# SPI_Bus.net
KiCad netlist of a schematic drawn in Altium Designer
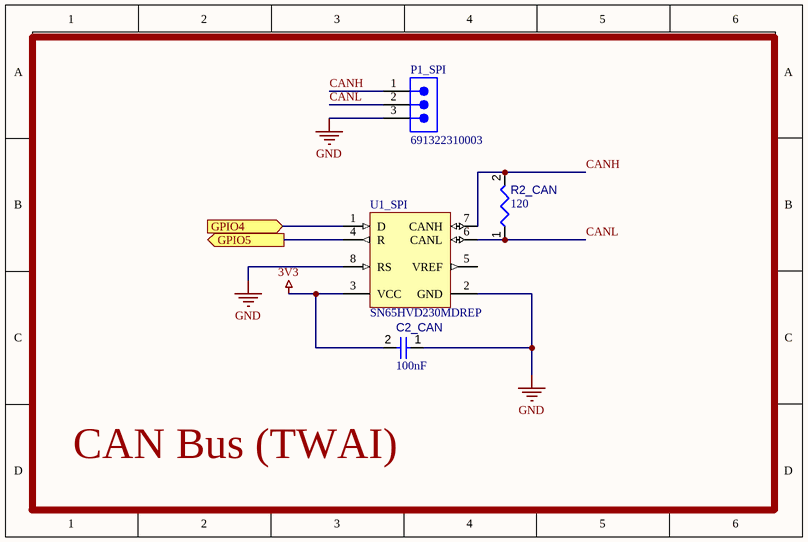
[diagram p0: SPI Bus.SchDoc]

(export (version "E")
  (design (tool "Eeschema 10.0.6"))
  (components
    (comp (ref "C2_CAN")
      (value "100nF")
      (footprint "CAPC0402(1005)60_L")
      (description "Chip Capacitor, 100nF +/-20%, 50V, 0402, Thickness 0.6 mm")
      (fields (field (name "TOLERANCE") "10%") (field (name "Comment") "Capacitor 100nF +/-20% 50V 0402"))
      (libsource (lib "Faiz Agunda") (part "CAP-NP-2"))
    )
    (comp (ref "P1_SPI")
      (value "691322310003")
      (footprint "691322310003")
      (description "322; 3.81mm Pitch Straight Pluggable Term Block; PCB Header; Through Hole; 3 Way")
      (fields (field (name "VOLTAGE") "300V"))
      (libsource (lib "Altium Content Vault") (part "TBL - 1R - 03P - Male"))
    )
    (comp (ref "R2_CAN")
      (value "120")
      (footprint "RESC0603(1608)_L")
      (description "Chip Resistor, 120 Ohms, +/-5 %, 0.1 W, -55 to 155 degC, 0603")
      (fields (field (name "POWER") "100mW") (field (name "TOLERANCE") "5%"))
      (libsource (lib "Faiz Agunda") (part "RES-2"))
    )
    (comp (ref "U1_SPI")
      (value "SN65HVD230MDREP")
      (footprint "D0008A_L")
      (fields (field (name "MANUFACTURER") "Texas Instruments"))
      (libsource (lib "Altium Content Vault") (part "TI-SN65HVD230M-EP-SOIC_D-8"))
    )
  )
  (nets
    (net (code "1") (name "/CANH") (class "Default")
      (node (ref "P1_SPI") (pin "1") (pinfunction "1_1") (pintype "passive"))
      (node (ref "R2_CAN") (pin "2") (pinfunction "2_2") (pintype "passive"))
      (node (ref "U1_SPI") (pin "7") (pinfunction "CANH_7") (pintype "bidirectional"))
    )
    (net (code "2") (name "/CANL") (class "Default")
      (node (ref "P1_SPI") (pin "2") (pinfunction "2_2") (pintype "passive"))
      (node (ref "R2_CAN") (pin "1") (pinfunction "1_1") (pintype "passive"))
      (node (ref "U1_SPI") (pin "6") (pinfunction "CANL_6") (pintype "bidirectional"))
    )
    (net (code "3") (name "/GPIO4") (class "Default")
      (node (ref "U1_SPI") (pin "1") (pinfunction "D_1") (pintype "input"))
    )
    (net (code "4") (name "/GPIO5") (class "Default")
      (node (ref "U1_SPI") (pin "4") (pinfunction "R_4") (pintype "output"))
    )
    (net (code "5") (name "3V3") (class "Default")
      (node (ref "C2_CAN") (pin "2") (pinfunction "2_2") (pintype "passive"))
      (node (ref "U1_SPI") (pin "3") (pinfunction "VCC_3") (pintype "power_in"))
    )
    (net (code "6") (name "GND") (class "Default")
      (node (ref "C2_CAN") (pin "1") (pinfunction "1_1") (pintype "passive"))
      (node (ref "P1_SPI") (pin "3") (pinfunction "3_3") (pintype "passive"))
      (node (ref "U1_SPI") (pin "2") (pinfunction "GND_2") (pintype "power_in"))
      (node (ref "U1_SPI") (pin "8") (pinfunction "RS_8") (pintype "input"))
    )
    (net (code "7") (name "unconnected-(U1_SPI-VREF-Pad5)") (class "Default")
      (node (ref "U1_SPI") (pin "5") (pinfunction "VREF_5") (pintype "output"))
    )
  )
)
